# ai_breakout_MCP4725.net
KiCad netlist of a schematic drawn in EAGLE
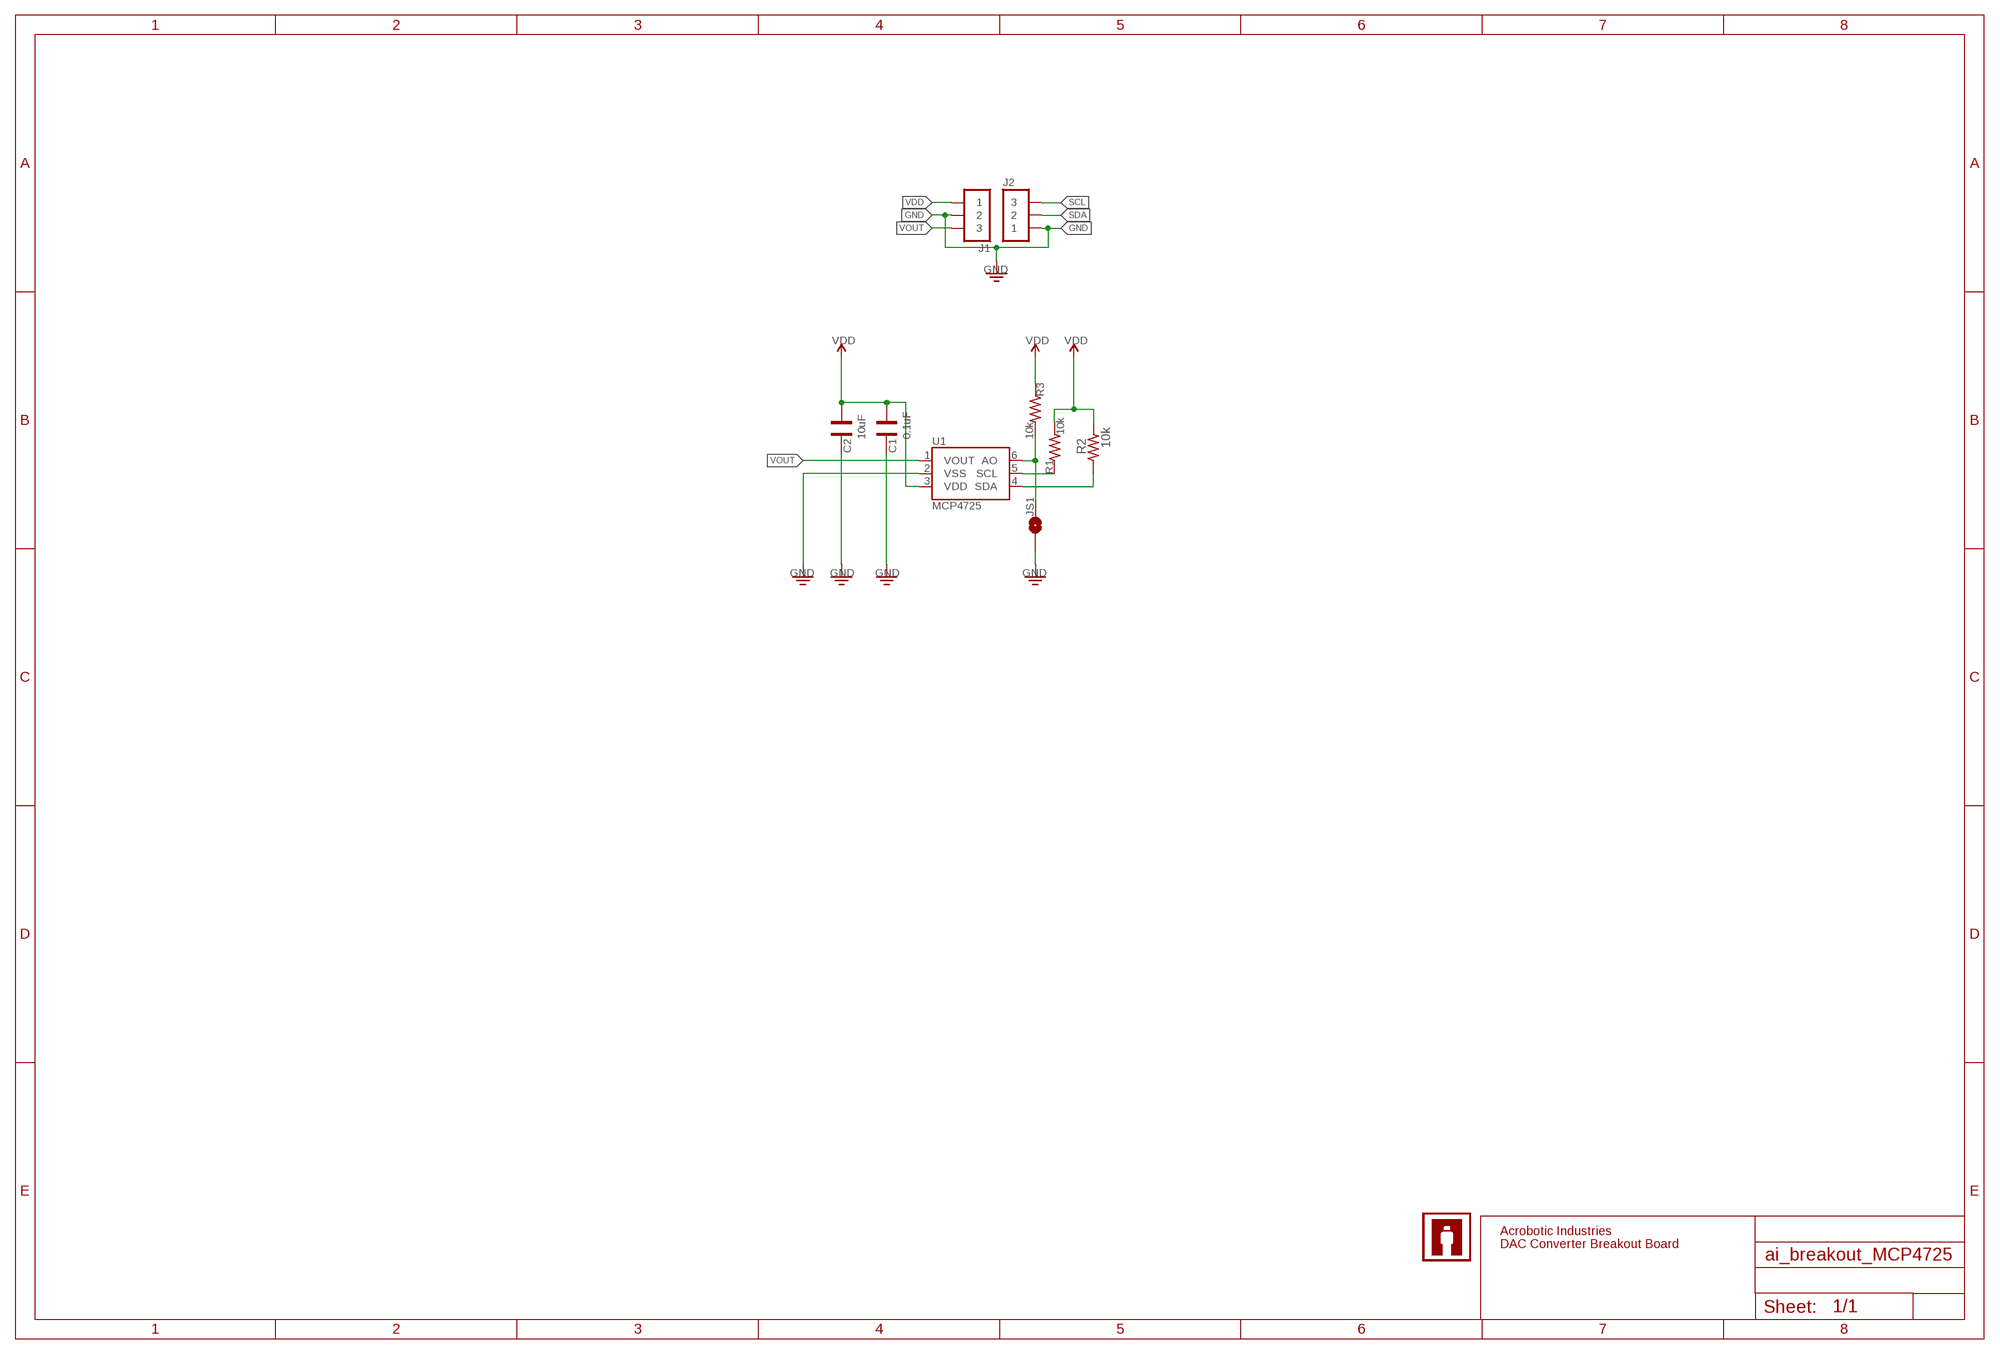
[diagram p0: schematic, sheet 1]

(export (version "E")
  (design (tool "Eeschema 10.0.6"))
  (components
    (comp (ref "C1")
      (value "0.1uF")
      (footprint "eagle-import:CAP-0603")
      (libsource (lib "eagle-import") (part "CAP0603"))
    )
    (comp (ref "C2")
      (value "10uF")
      (footprint "eagle-import:CAP-0603")
      (libsource (lib "eagle-import") (part "CAP0603"))
    )
    (comp (ref "J1")
      (value "1X03")
      (footprint "eagle-import:1X03")
      (libsource (lib "eagle-import") (part "1X03"))
    )
    (comp (ref "J2")
      (value "1X03NOFIRST")
      (footprint "eagle-import:1X03-NOFIRST")
      (libsource (lib "eagle-import") (part "1X03NOFIRST"))
    )
    (comp (ref "JS1")
      (value "1X02-SJ-NO")
      (footprint "eagle-import:1X02-SJ-NO")
      (libsource (lib "eagle-import") (part "1X02-SJ-NO"))
    )
    (comp (ref "R1")
      (value "10k")
      (footprint "eagle-import:RES-0603")
      (libsource (lib "eagle-import") (part "RES0603"))
    )
    (comp (ref "R2")
      (value "10k")
      (footprint "eagle-import:RES-0603")
      (libsource (lib "eagle-import") (part "RES0603"))
    )
    (comp (ref "R3")
      (value "10k")
      (footprint "eagle-import:RES-0603")
      (libsource (lib "eagle-import") (part "RES0603"))
    )
    (comp (ref "U$4")
      (value "AI-LOGOXS")
      (footprint "eagle-import:AI-LOGO-XS")
      (libsource (lib "eagle-import") (part "AI-LOGOXS"))
    )
    (comp (ref "U1")
      (value "MCP4725SOT-23")
      (footprint "eagle-import:SOT23-6")
      (libsource (lib "eagle-import") (part "MCP4725SOT-23"))
    )
  )
  (nets
    (net (code "1") (name "GND") (class "Default")
      (node (ref "C1") (pin "2") (pinfunction "2_2") (pintype "passive"))
      (node (ref "C2") (pin "2") (pinfunction "2_2") (pintype "passive"))
      (node (ref "J1") (pin "2") (pinfunction "2_2") (pintype "bidirectional"))
      (node (ref "J2") (pin "1") (pinfunction "1_1") (pintype "bidirectional"))
      (node (ref "JS1") (pin "1") (pinfunction "1_1") (pintype "passive"))
      (node (ref "U1") (pin "2") (pinfunction "VSS_2") (pintype "bidirectional"))
    )
    (net (code "2") (name "SCL") (class "Default")
      (node (ref "J2") (pin "3") (pinfunction "3_3") (pintype "bidirectional"))
      (node (ref "R1") (pin "1") (pinfunction "1_1") (pintype "passive"))
      (node (ref "U1") (pin "5") (pinfunction "SCL_5") (pintype "bidirectional"))
    )
    (net (code "3") (name "SDA") (class "Default")
      (node (ref "J2") (pin "2") (pinfunction "2_2") (pintype "bidirectional"))
      (node (ref "R2") (pin "1") (pinfunction "1_1") (pintype "passive"))
      (node (ref "U1") (pin "4") (pinfunction "SDA_4") (pintype "bidirectional"))
    )
    (net (code "4") (name "VDD") (class "Default")
      (node (ref "C1") (pin "1") (pinfunction "1_1") (pintype "passive"))
      (node (ref "C2") (pin "1") (pinfunction "1_1") (pintype "passive"))
      (node (ref "J1") (pin "1") (pinfunction "1_1") (pintype "bidirectional"))
      (node (ref "JS1") (pin "2") (pinfunction "2_2") (pintype "passive"))
      (node (ref "R1") (pin "2") (pinfunction "2_2") (pintype "passive"))
      (node (ref "R2") (pin "2") (pinfunction "2_2") (pintype "passive"))
      (node (ref "R3") (pin "1") (pinfunction "1_1") (pintype "passive"))
      (node (ref "R3") (pin "2") (pinfunction "2_2") (pintype "passive"))
      (node (ref "U1") (pin "3") (pinfunction "VDD_3") (pintype "bidirectional"))
      (node (ref "U1") (pin "6") (pinfunction "AO_6") (pintype "bidirectional"))
    )
    (net (code "5") (name "VOUT") (class "Default")
      (node (ref "J1") (pin "3") (pinfunction "3_3") (pintype "bidirectional"))
      (node (ref "U1") (pin "1") (pinfunction "VOUT_1") (pintype "bidirectional"))
    )
  )
)
